# Ex_Sensors.net
KiCad netlist of a schematic drawn in EAGLE
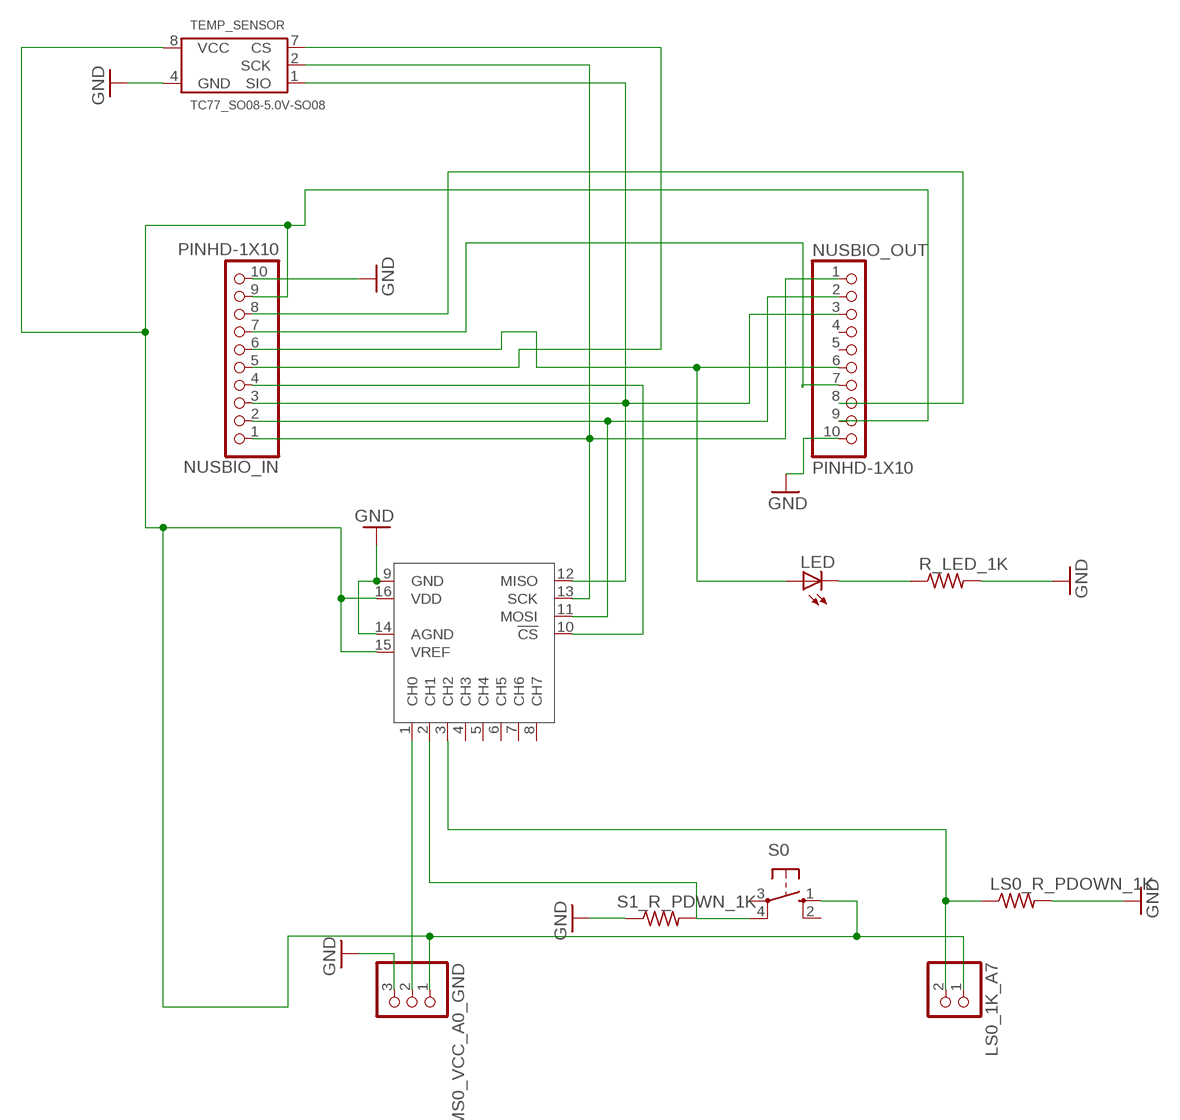
[diagram p0: schematic, sheet 1]

(export (version "E")
  (design (tool "Eeschema 10.0.6"))
  (components
    (comp (ref "LED")
      (value "LEDCHIPLED_0805")
      (footprint "eagle-import:CHIPLED_0805")
      (libsource (lib "eagle-import") (part "LEDCHIPLED_0805"))
    )
    (comp (ref "LS0_1K_A7")
      (value "PINHD-1X2")
      (footprint "eagle-import:1X02")
      (libsource (lib "eagle-import") (part "PINHD-1X2"))
    )
    (comp (ref "LS0_R_PDOWN_1K")
      (value "R-US_R0805")
      (footprint "eagle-import:R0805")
      (libsource (lib "eagle-import") (part "R-US_R0805"))
    )
    (comp (ref "MS0_VCC_A0_GND")
      (value "PINHD-1X3")
      (footprint "eagle-import:1X03")
      (libsource (lib "eagle-import") (part "PINHD-1X3"))
    )
    (comp (ref "NUSBIO_IN")
      (value "PINHD-1X10")
      (footprint "eagle-import:1X10-BIG")
      (libsource (lib "eagle-import") (part "PINHD-1X10"))
    )
    (comp (ref "NUSBIO_OUT")
      (value "PINHD-1X10")
      (footprint "eagle-import:1X10-BIG")
      (libsource (lib "eagle-import") (part "PINHD-1X10"))
    )
    (comp (ref "R_LED_1K")
      (value "R-US_R0805")
      (footprint "eagle-import:R0805")
      (libsource (lib "eagle-import") (part "R-US_R0805"))
    )
    (comp (ref "S0")
      (value "10-XX")
      (footprint "eagle-import:B3F-10XX")
      (fields (field (name "MPN") "B3F-1000"))
      (libsource (lib "eagle-import") (part "10-XX"))
    )
    (comp (ref "S1_R_PDWN_1K")
      (value "R-US_R0805")
      (footprint "eagle-import:R0805")
      (libsource (lib "eagle-import") (part "R-US_R0805"))
    )
    (comp (ref "TEMP_SENSOR")
      (value "TC77_SO08-5.0V-SO08")
      (footprint "eagle-import:SO-08")
      (fields (field (name "MPN") "TC77-5.0MOA"))
      (libsource (lib "eagle-import") (part "TC77_SO08SO08-5.0V-"))
    )
    (comp (ref "U$1")
      (value "MCP3008SL")
      (footprint "eagle-import:SO16")
      (libsource (lib "eagle-import") (part "MCP3008SL"))
    )
  )
  (nets
    (net (code "1") (name "GND") (class "Default")
      (node (ref "LS0_R_PDOWN_1K") (pin "2") (pinfunction "2_2") (pintype "passive"))
      (node (ref "MS0_VCC_A0_GND") (pin "3") (pinfunction "3_3") (pintype "passive"))
      (node (ref "NUSBIO_IN") (pin "10") (pinfunction "10_10") (pintype "passive"))
      (node (ref "NUSBIO_OUT") (pin "10") (pinfunction "10_10") (pintype "passive"))
      (node (ref "R_LED_1K") (pin "2") (pinfunction "2_2") (pintype "passive"))
      (node (ref "S1_R_PDWN_1K") (pin "1") (pinfunction "1_1") (pintype "passive"))
      (node (ref "TEMP_SENSOR") (pin "4") (pinfunction "GND_4") (pintype "power_in"))
      (node (ref "U$1") (pin "14") (pinfunction "AGND_14") (pintype "power_in"))
      (node (ref "U$1") (pin "9") (pinfunction "GND_9") (pintype "power_in"))
    )
    (net (code "2") (name "Net-(LED-PadA)") (class "Default")
      (node (ref "LED") (pin "A") (pinfunction "A_A") (pintype "passive"))
      (node (ref "NUSBIO_IN") (pin "6") (pinfunction "6_6") (pintype "passive"))
      (node (ref "NUSBIO_OUT") (pin "6") (pinfunction "6_6") (pintype "passive"))
    )
    (net (code "3") (name "Net-(LED-PadC)") (class "Default")
      (node (ref "LED") (pin "C") (pinfunction "C_C") (pintype "passive"))
      (node (ref "R_LED_1K") (pin "1") (pinfunction "1_1") (pintype "passive"))
    )
    (net (code "4") (name "Net-(NUSBIO_IN-Pad7)") (class "Default")
      (node (ref "NUSBIO_IN") (pin "7") (pinfunction "7_7") (pintype "passive"))
      (node (ref "NUSBIO_OUT") (pin "7") (pinfunction "7_7") (pintype "passive"))
    )
    (net (code "5") (name "Net-(NUSBIO_IN-Pad8)") (class "Default")
      (node (ref "NUSBIO_IN") (pin "8") (pinfunction "8_8") (pintype "passive"))
      (node (ref "NUSBIO_OUT") (pin "8") (pinfunction "8_8") (pintype "passive"))
    )
    (net (code "6") (name "Net-(S0-P1)") (class "Default")
      (node (ref "S0") (pin "4") (pinfunction "P1_4") (pintype "passive"))
      (node (ref "S1_R_PDWN_1K") (pin "2") (pinfunction "2_2") (pintype "passive"))
      (node (ref "U$1") (pin "2") (pinfunction "CH1_2") (pintype "input"))
    )
    (net (code "7") (name "Net-(S0-S)") (class "Default")
      (node (ref "LS0_1K_A7") (pin "1") (pinfunction "1_1") (pintype "passive"))
      (node (ref "MS0_VCC_A0_GND") (pin "1") (pinfunction "1_1") (pintype "passive"))
      (node (ref "NUSBIO_IN") (pin "9") (pinfunction "9_9") (pintype "passive"))
      (node (ref "NUSBIO_OUT") (pin "9") (pinfunction "9_9") (pintype "passive"))
      (node (ref "S0") (pin "1") (pinfunction "S_1") (pintype "passive"))
      (node (ref "TEMP_SENSOR") (pin "8") (pinfunction "VCC_8") (pintype "power_in"))
      (node (ref "U$1") (pin "15") (pinfunction "VREF_15") (pintype "power_in"))
      (node (ref "U$1") (pin "16") (pinfunction "VDD_16") (pintype "power_in"))
    )
    (net (code "8") (name "Net-(TEMP_SENSOR-CS)") (class "Default")
      (node (ref "NUSBIO_IN") (pin "5") (pinfunction "5_5") (pintype "passive"))
      (node (ref "TEMP_SENSOR") (pin "7") (pinfunction "CS_7") (pintype "bidirectional"))
    )
    (net (code "9") (name "Net-(TEMP_SENSOR-SCK)") (class "Default")
      (node (ref "NUSBIO_IN") (pin "1") (pinfunction "1_1") (pintype "passive"))
      (node (ref "NUSBIO_OUT") (pin "1") (pinfunction "1_1") (pintype "passive"))
      (node (ref "TEMP_SENSOR") (pin "2") (pinfunction "SCK_2") (pintype "bidirectional"))
      (node (ref "U$1") (pin "13") (pinfunction "SCK_13") (pintype "input"))
    )
    (net (code "10") (name "Net-(TEMP_SENSOR-SIO)") (class "Default")
      (node (ref "NUSBIO_IN") (pin "3") (pinfunction "3_3") (pintype "passive"))
      (node (ref "NUSBIO_OUT") (pin "3") (pinfunction "3_3") (pintype "passive"))
      (node (ref "TEMP_SENSOR") (pin "1") (pinfunction "SIO_1") (pintype "bidirectional"))
      (node (ref "U$1") (pin "12") (pinfunction "MISO_12") (pintype "output"))
    )
    (net (code "11") (name "Net-(U$1-CH0)") (class "Default")
      (node (ref "MS0_VCC_A0_GND") (pin "2") (pinfunction "2_2") (pintype "passive"))
      (node (ref "U$1") (pin "1") (pinfunction "CH0_1") (pintype "input"))
    )
    (net (code "12") (name "Net-(U$1-CH2)") (class "Default")
      (node (ref "LS0_1K_A7") (pin "2") (pinfunction "2_2") (pintype "passive"))
      (node (ref "LS0_R_PDOWN_1K") (pin "1") (pinfunction "1_1") (pintype "passive"))
      (node (ref "U$1") (pin "3") (pinfunction "CH2_3") (pintype "input"))
    )
    (net (code "13") (name "Net-(U$1-MOSI)") (class "Default")
      (node (ref "NUSBIO_IN") (pin "2") (pinfunction "2_2") (pintype "passive"))
      (node (ref "NUSBIO_OUT") (pin "2") (pinfunction "2_2") (pintype "passive"))
      (node (ref "U$1") (pin "11") (pinfunction "MOSI_11") (pintype "input"))
    )
    (net (code "14") (name "Net-(U$1-~{CS})") (class "Default")
      (node (ref "NUSBIO_IN") (pin "4") (pinfunction "4_4") (pintype "passive"))
      (node (ref "U$1") (pin "10") (pinfunction "~{CS}_10") (pintype "input"))
    )
    (net (code "15") (name "unconnected-(NUSBIO_OUT-Pad4)") (class "Default")
      (node (ref "NUSBIO_OUT") (pin "4") (pinfunction "4_4") (pintype "passive"))
    )
    (net (code "16") (name "unconnected-(NUSBIO_OUT-Pad5)") (class "Default")
      (node (ref "NUSBIO_OUT") (pin "5") (pinfunction "5_5") (pintype "passive"))
    )
    (net (code "17") (name "unconnected-(S0-P-Pad3)") (class "Default")
      (node (ref "S0") (pin "3") (pinfunction "P_3") (pintype "passive"))
    )
    (net (code "18") (name "unconnected-(S0-S1-Pad2)") (class "Default")
      (node (ref "S0") (pin "2") (pinfunction "S1_2") (pintype "passive"))
    )
    (net (code "19") (name "unconnected-(U$1-CH3-Pad4)") (class "Default")
      (node (ref "U$1") (pin "4") (pinfunction "CH3_4") (pintype "input"))
    )
    (net (code "20") (name "unconnected-(U$1-CH4-Pad5)") (class "Default")
      (node (ref "U$1") (pin "5") (pinfunction "CH4_5") (pintype "input"))
    )
    (net (code "21") (name "unconnected-(U$1-CH5-Pad6)") (class "Default")
      (node (ref "U$1") (pin "6") (pinfunction "CH5_6") (pintype "input"))
    )
    (net (code "22") (name "unconnected-(U$1-CH6-Pad7)") (class "Default")
      (node (ref "U$1") (pin "7") (pinfunction "CH6_7") (pintype "input"))
    )
    (net (code "23") (name "unconnected-(U$1-CH7-Pad8)") (class "Default")
      (node (ref "U$1") (pin "8") (pinfunction "CH7_8") (pintype "input"))
    )
  )
)
